# smd_isp_adapters.net
KiCad netlist of a schematic drawn in EAGLE
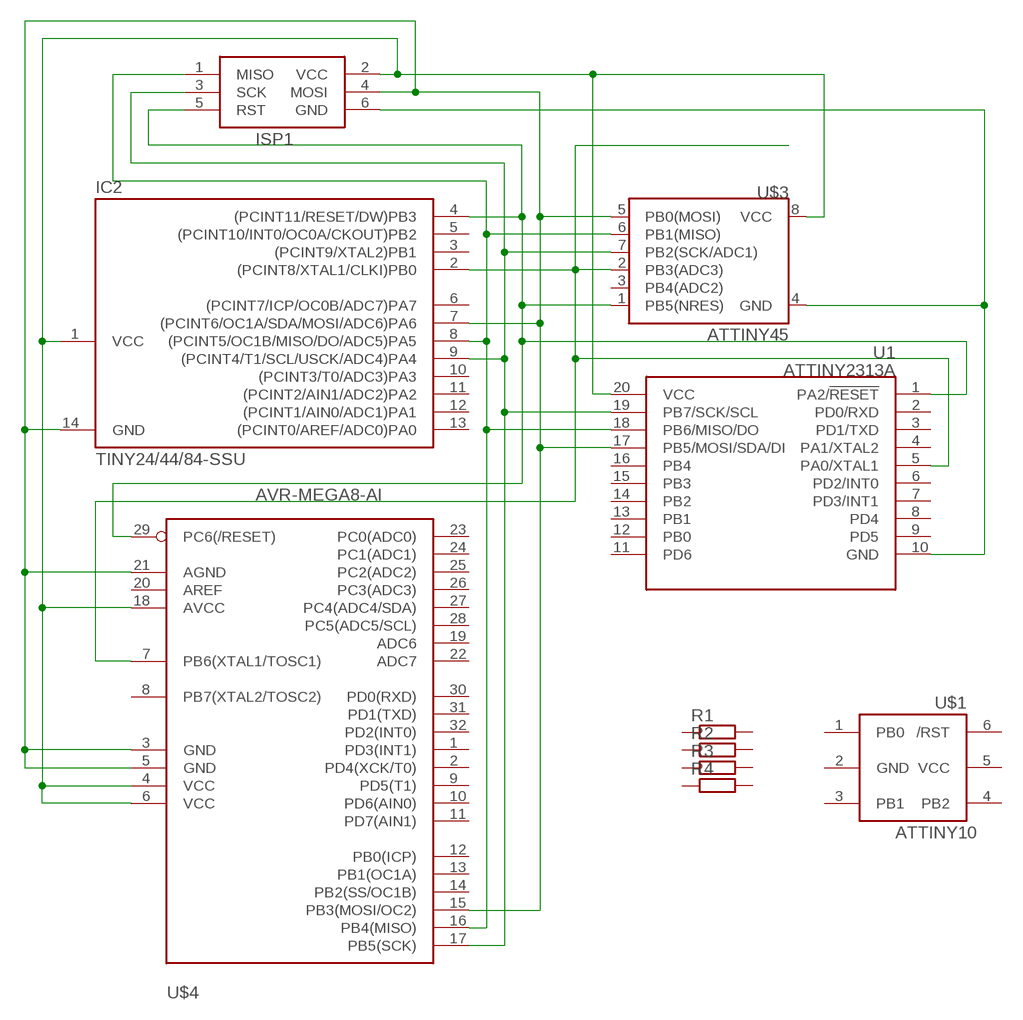
[diagram p0: schematic, sheet 1]

(export (version "E")
  (design (tool "Eeschema 10.0.6"))
  (components
    (comp (ref "IC2")
      (value "TINY24/44/84-SSU")
      (footprint "eagle-import:SOIC14")
      (libsource (lib "eagle-import") (part "TINY24/44/84-SSU"))
    )
    (comp (ref "ISP1")
      (value "AVRISP-6")
      (footprint "eagle-import:AVRISP")
      (libsource (lib "eagle-import") (part "AVRISP-6"))
    )
    (comp (ref "R1")
      (value "R-EU_R0805")
      (footprint "eagle-import:R0805")
      (libsource (lib "eagle-import") (part "R-EU_R0805"))
    )
    (comp (ref "R2")
      (value "R-EU_R0805")
      (footprint "eagle-import:R0805")
      (libsource (lib "eagle-import") (part "R-EU_R0805"))
    )
    (comp (ref "R3")
      (value "R-EU_R0805")
      (footprint "eagle-import:R0805")
      (libsource (lib "eagle-import") (part "R-EU_R0805"))
    )
    (comp (ref "R4")
      (value "R-EU_R0805")
      (footprint "eagle-import:R0805")
      (libsource (lib "eagle-import") (part "R-EU_R0805"))
    )
    (comp (ref "U$1")
      (value "ATTINY10")
      (footprint "eagle-import:SOT23-6")
      (libsource (lib "eagle-import") (part "ATTINY10"))
    )
    (comp (ref "U$3")
      (value "ATTINY45")
      (footprint "eagle-import:SO08-EIAJ")
      (libsource (lib "eagle-import") (part "ATTINY45"))
    )
    (comp (ref "U$4")
      (value "AVR-MEGA8-AI")
      (footprint "eagle-import:TQFP32-08")
      (libsource (lib "eagle-import") (part "AVR-MEGA8-AI"))
    )
    (comp (ref "U1")
      (value "ATTINY2313A")
      (footprint "eagle-import:SOP20W")
      (libsource (lib "eagle-import") (part "ATTINY2313A"))
    )
  )
  (nets
    (net (code "1") (name "/GND") (class "Default")
      (node (ref "U$1") (pin "2") (pinfunction "GND_2") (pintype "power_in"))
    )
    (net (code "2") (name "/VCC") (class "Default")
      (node (ref "U$1") (pin "5") (pinfunction "VCC_5") (pintype "power_in"))
    )
    (net (code "3") (name "Net-(IC2-(PCINT4{slash}T1{slash}SCL{slash}USCK{slash}ADC4)PA4)") (class "Default")
      (node (ref "IC2") (pin "9") (pinfunction "(PCINT4/T1/SCL/USCK/ADC4)PA4_9") (pintype "bidirectional"))
      (node (ref "ISP1") (pin "3") (pinfunction "SCK_3") (pintype "output"))
      (node (ref "U$3") (pin "7") (pinfunction "PB2(SCK/ADC1)_7") (pintype "bidirectional"))
      (node (ref "U$4") (pin "17") (pinfunction "PB5(SCK)_17") (pintype "bidirectional"))
      (node (ref "U1") (pin "19") (pinfunction "PB7/SCK/SCL_19") (pintype "bidirectional"))
    )
    (net (code "4") (name "Net-(IC2-(PCINT5{slash}OC1B{slash}MISO{slash}DO{slash}ADC5)PA5)") (class "Default")
      (node (ref "IC2") (pin "8") (pinfunction "(PCINT5/OC1B/MISO/DO/ADC5)PA5_8") (pintype "bidirectional"))
      (node (ref "ISP1") (pin "1") (pinfunction "MISO_1") (pintype "input"))
      (node (ref "U$3") (pin "6") (pinfunction "PB1(MISO)_6") (pintype "bidirectional"))
      (node (ref "U$4") (pin "16") (pinfunction "PB4(MISO)_16") (pintype "bidirectional"))
      (node (ref "U1") (pin "18") (pinfunction "PB6/MISO/DO_18") (pintype "bidirectional"))
    )
    (net (code "5") (name "Net-(IC2-(PCINT6{slash}OC1A{slash}SDA{slash}MOSI{slash}ADC6)PA6)") (class "Default")
      (node (ref "IC2") (pin "14") (pinfunction "GND_14") (pintype "power_in"))
      (node (ref "IC2") (pin "7") (pinfunction "(PCINT6/OC1A/SDA/MOSI/ADC6)PA6_7") (pintype "bidirectional"))
      (node (ref "ISP1") (pin "4") (pinfunction "MOSI_4") (pintype "output"))
      (node (ref "U$3") (pin "5") (pinfunction "PB0(MOSI)_5") (pintype "bidirectional"))
      (node (ref "U$4") (pin "15") (pinfunction "PB3(MOSI/OC2)_15") (pintype "bidirectional"))
      (node (ref "U$4") (pin "21") (pinfunction "AGND_21") (pintype "bidirectional"))
      (node (ref "U$4") (pin "3") (pinfunction "GND_3") (pintype "bidirectional"))
      (node (ref "U$4") (pin "5") (pinfunction "GND_5") (pintype "bidirectional"))
      (node (ref "U1") (pin "17") (pinfunction "PB5/MOSI/SDA/DI_17") (pintype "bidirectional"))
    )
    (net (code "6") (name "Net-(IC2-(PCINT8{slash}XTAL1{slash}CLKI)PB0)") (class "Default")
      (node (ref "IC2") (pin "2") (pinfunction "(PCINT8/XTAL1/CLKI)PB0_2") (pintype "bidirectional"))
      (node (ref "U$3") (pin "2") (pinfunction "PB3(ADC3)_2") (pintype "bidirectional"))
      (node (ref "U$4") (pin "7") (pinfunction "PB6(XTAL1/TOSC1)_7") (pintype "bidirectional"))
      (node (ref "U1") (pin "5") (pinfunction "PA0/XTAL1_5") (pintype "bidirectional"))
    )
    (net (code "7") (name "Net-(IC2-(PCINT11{slash}RESET{slash}DW)PB3)") (class "Default")
      (node (ref "IC2") (pin "4") (pinfunction "(PCINT11/RESET/DW)PB3_4") (pintype "bidirectional"))
      (node (ref "ISP1") (pin "5") (pinfunction "RST_5") (pintype "output"))
      (node (ref "U$3") (pin "1") (pinfunction "PB5(NRES)_1") (pintype "bidirectional"))
      (node (ref "U$4") (pin "29") (pinfunction "PC6(/RESET)_29") (pintype "bidirectional"))
      (node (ref "U1") (pin "1") (pinfunction "PA2/~{RESET}_1") (pintype "bidirectional"))
    )
    (net (code "8") (name "Net-(IC2-VCC)") (class "Default")
      (node (ref "IC2") (pin "1") (pinfunction "VCC_1") (pintype "power_in"))
      (node (ref "ISP1") (pin "2") (pinfunction "VCC_2") (pintype "power_in"))
      (node (ref "U$3") (pin "8") (pinfunction "VCC_8") (pintype "bidirectional"))
      (node (ref "U$4") (pin "18") (pinfunction "AVCC_18") (pintype "bidirectional"))
      (node (ref "U$4") (pin "4") (pinfunction "VCC_4") (pintype "bidirectional"))
      (node (ref "U$4") (pin "6") (pinfunction "VCC_6") (pintype "bidirectional"))
      (node (ref "U1") (pin "20") (pinfunction "VCC_20") (pintype "bidirectional"))
    )
    (net (code "9") (name "Net-(ISP1-GND)") (class "Default")
      (node (ref "ISP1") (pin "6") (pinfunction "GND_6") (pintype "power_in"))
      (node (ref "U$3") (pin "4") (pinfunction "GND_4") (pintype "bidirectional"))
      (node (ref "U1") (pin "10") (pinfunction "GND_10") (pintype "bidirectional"))
    )
    (net (code "10") (name "unconnected-(IC2-(PCINT0{slash}AREF{slash}ADC0)PA0-Pad13)") (class "Default")
      (node (ref "IC2") (pin "13") (pinfunction "(PCINT0/AREF/ADC0)PA0_13") (pintype "bidirectional"))
    )
    (net (code "11") (name "unconnected-(IC2-(PCINT1{slash}AIN0{slash}ADC1)PA1-Pad12)") (class "Default")
      (node (ref "IC2") (pin "12") (pinfunction "(PCINT1/AIN0/ADC1)PA1_12") (pintype "bidirectional"))
    )
    (net (code "12") (name "unconnected-(IC2-(PCINT2{slash}AIN1{slash}ADC2)PA2-Pad11)") (class "Default")
      (node (ref "IC2") (pin "11") (pinfunction "(PCINT2/AIN1/ADC2)PA2_11") (pintype "bidirectional"))
    )
    (net (code "13") (name "unconnected-(IC2-(PCINT3{slash}T0{slash}ADC3)PA3-Pad10)") (class "Default")
      (node (ref "IC2") (pin "10") (pinfunction "(PCINT3/T0/ADC3)PA3_10") (pintype "bidirectional"))
    )
    (net (code "14") (name "unconnected-(IC2-(PCINT7{slash}ICP{slash}OC0B{slash}ADC7)PA7-Pad6)") (class "Default")
      (node (ref "IC2") (pin "6") (pinfunction "(PCINT7/ICP/OC0B/ADC7)PA7_6") (pintype "bidirectional"))
    )
    (net (code "15") (name "unconnected-(IC2-(PCINT9{slash}XTAL2)PB1-Pad3)") (class "Default")
      (node (ref "IC2") (pin "3") (pinfunction "(PCINT9/XTAL2)PB1_3") (pintype "bidirectional"))
    )
    (net (code "16") (name "unconnected-(IC2-(PCINT10{slash}INT0{slash}OC0A{slash}CKOUT)PB2-Pad5)") (class "Default")
      (node (ref "IC2") (pin "5") (pinfunction "(PCINT10/INT0/OC0A/CKOUT)PB2_5") (pintype "bidirectional"))
    )
    (net (code "17") (name "unconnected-(R1-Pad1)") (class "Default")
      (node (ref "R1") (pin "1") (pinfunction "1_1") (pintype "passive"))
    )
    (net (code "18") (name "unconnected-(R1-Pad2)") (class "Default")
      (node (ref "R1") (pin "2") (pinfunction "2_2") (pintype "passive"))
    )
    (net (code "19") (name "unconnected-(R2-Pad1)") (class "Default")
      (node (ref "R2") (pin "1") (pinfunction "1_1") (pintype "passive"))
    )
    (net (code "20") (name "unconnected-(R2-Pad2)") (class "Default")
      (node (ref "R2") (pin "2") (pinfunction "2_2") (pintype "passive"))
    )
    (net (code "21") (name "unconnected-(R3-Pad1)") (class "Default")
      (node (ref "R3") (pin "1") (pinfunction "1_1") (pintype "passive"))
    )
    (net (code "22") (name "unconnected-(R3-Pad2)") (class "Default")
      (node (ref "R3") (pin "2") (pinfunction "2_2") (pintype "passive"))
    )
    (net (code "23") (name "unconnected-(R4-Pad1)") (class "Default")
      (node (ref "R4") (pin "1") (pinfunction "1_1") (pintype "passive"))
    )
    (net (code "24") (name "unconnected-(R4-Pad2)") (class "Default")
      (node (ref "R4") (pin "2") (pinfunction "2_2") (pintype "passive"))
    )
    (net (code "25") (name "unconnected-(U$1-PB0-Pad1)") (class "Default")
      (node (ref "U$1") (pin "1") (pinfunction "PB0_1") (pintype "bidirectional"))
    )
    (net (code "26") (name "unconnected-(U$1-PB1-Pad3)") (class "Default")
      (node (ref "U$1") (pin "3") (pinfunction "PB1_3") (pintype "bidirectional"))
    )
    (net (code "27") (name "unconnected-(U$1-PB2-Pad4)") (class "Default")
      (node (ref "U$1") (pin "4") (pinfunction "PB2_4") (pintype "bidirectional"))
    )
    (net (code "28") (name "unconnected-(U$1-{slash}RST-Pad6)") (class "Default")
      (node (ref "U$1") (pin "6") (pinfunction "/RST_6") (pintype "bidirectional"))
    )
    (net (code "29") (name "unconnected-(U$3-PB4(ADC2)-Pad3)") (class "Default")
      (node (ref "U$3") (pin "3") (pinfunction "PB4(ADC2)_3") (pintype "bidirectional"))
    )
    (net (code "30") (name "unconnected-(U$4-ADC6-Pad19)") (class "Default")
      (node (ref "U$4") (pin "19") (pinfunction "ADC6_19") (pintype "bidirectional"))
    )
    (net (code "31") (name "unconnected-(U$4-ADC7-Pad22)") (class "Default")
      (node (ref "U$4") (pin "22") (pinfunction "ADC7_22") (pintype "bidirectional"))
    )
    (net (code "32") (name "unconnected-(U$4-AREF-Pad20)") (class "Default")
      (node (ref "U$4") (pin "20") (pinfunction "AREF_20") (pintype "bidirectional"))
    )
    (net (code "33") (name "unconnected-(U$4-PB0(ICP)-Pad12)") (class "Default")
      (node (ref "U$4") (pin "12") (pinfunction "PB0(ICP)_12") (pintype "bidirectional"))
    )
    (net (code "34") (name "unconnected-(U$4-PB1(OC1A)-Pad13)") (class "Default")
      (node (ref "U$4") (pin "13") (pinfunction "PB1(OC1A)_13") (pintype "bidirectional"))
    )
    (net (code "35") (name "unconnected-(U$4-PB2(SS{slash}OC1B)-Pad14)") (class "Default")
      (node (ref "U$4") (pin "14") (pinfunction "PB2(SS/OC1B)_14") (pintype "bidirectional"))
    )
    (net (code "36") (name "unconnected-(U$4-PB7(XTAL2{slash}TOSC2)-Pad8)") (class "Default")
      (node (ref "U$4") (pin "8") (pinfunction "PB7(XTAL2/TOSC2)_8") (pintype "bidirectional"))
    )
    (net (code "37") (name "unconnected-(U$4-PC0(ADC0)-Pad23)") (class "Default")
      (node (ref "U$4") (pin "23") (pinfunction "PC0(ADC0)_23") (pintype "bidirectional"))
    )
    (net (code "38") (name "unconnected-(U$4-PC1(ADC1)-Pad24)") (class "Default")
      (node (ref "U$4") (pin "24") (pinfunction "PC1(ADC1)_24") (pintype "bidirectional"))
    )
    (net (code "39") (name "unconnected-(U$4-PC2(ADC2)-Pad25)") (class "Default")
      (node (ref "U$4") (pin "25") (pinfunction "PC2(ADC2)_25") (pintype "bidirectional"))
    )
    (net (code "40") (name "unconnected-(U$4-PC3(ADC3)-Pad26)") (class "Default")
      (node (ref "U$4") (pin "26") (pinfunction "PC3(ADC3)_26") (pintype "bidirectional"))
    )
    (net (code "41") (name "unconnected-(U$4-PC4(ADC4{slash}SDA)-Pad27)") (class "Default")
      (node (ref "U$4") (pin "27") (pinfunction "PC4(ADC4/SDA)_27") (pintype "bidirectional"))
    )
    (net (code "42") (name "unconnected-(U$4-PC5(ADC5{slash}SCL)-Pad28)") (class "Default")
      (node (ref "U$4") (pin "28") (pinfunction "PC5(ADC5/SCL)_28") (pintype "bidirectional"))
    )
    (net (code "43") (name "unconnected-(U$4-PD0(RXD)-Pad30)") (class "Default")
      (node (ref "U$4") (pin "30") (pinfunction "PD0(RXD)_30") (pintype "bidirectional"))
    )
    (net (code "44") (name "unconnected-(U$4-PD1(TXD)-Pad31)") (class "Default")
      (node (ref "U$4") (pin "31") (pinfunction "PD1(TXD)_31") (pintype "bidirectional"))
    )
    (net (code "45") (name "unconnected-(U$4-PD2(INT0)-Pad32)") (class "Default")
      (node (ref "U$4") (pin "32") (pinfunction "PD2(INT0)_32") (pintype "bidirectional"))
    )
    (net (code "46") (name "unconnected-(U$4-PD3(INT1)-Pad1)") (class "Default")
      (node (ref "U$4") (pin "1") (pinfunction "PD3(INT1)_1") (pintype "bidirectional"))
    )
    (net (code "47") (name "unconnected-(U$4-PD4(XCK{slash}T0)-Pad2)") (class "Default")
      (node (ref "U$4") (pin "2") (pinfunction "PD4(XCK/T0)_2") (pintype "bidirectional"))
    )
    (net (code "48") (name "unconnected-(U$4-PD5(T1)-Pad9)") (class "Default")
      (node (ref "U$4") (pin "9") (pinfunction "PD5(T1)_9") (pintype "bidirectional"))
    )
    (net (code "49") (name "unconnected-(U$4-PD6(AIN0)-Pad10)") (class "Default")
      (node (ref "U$4") (pin "10") (pinfunction "PD6(AIN0)_10") (pintype "bidirectional"))
    )
    (net (code "50") (name "unconnected-(U$4-PD7(AIN1)-Pad11)") (class "Default")
      (node (ref "U$4") (pin "11") (pinfunction "PD7(AIN1)_11") (pintype "bidirectional"))
    )
    (net (code "51") (name "unconnected-(U1-PA1{slash}XTAL2-Pad4)") (class "Default")
      (node (ref "U1") (pin "4") (pinfunction "PA1/XTAL2_4") (pintype "bidirectional"))
    )
    (net (code "52") (name "unconnected-(U1-PB0-Pad12)") (class "Default")
      (node (ref "U1") (pin "12") (pinfunction "PB0_12") (pintype "bidirectional"))
    )
    (net (code "53") (name "unconnected-(U1-PB1-Pad13)") (class "Default")
      (node (ref "U1") (pin "13") (pinfunction "PB1_13") (pintype "bidirectional"))
    )
    (net (code "54") (name "unconnected-(U1-PB2-Pad14)") (class "Default")
      (node (ref "U1") (pin "14") (pinfunction "PB2_14") (pintype "bidirectional"))
    )
    (net (code "55") (name "unconnected-(U1-PB3-Pad15)") (class "Default")
      (node (ref "U1") (pin "15") (pinfunction "PB3_15") (pintype "bidirectional"))
    )
    (net (code "56") (name "unconnected-(U1-PB4-Pad16)") (class "Default")
      (node (ref "U1") (pin "16") (pinfunction "PB4_16") (pintype "bidirectional"))
    )
    (net (code "57") (name "unconnected-(U1-PD0{slash}RXD-Pad2)") (class "Default")
      (node (ref "U1") (pin "2") (pinfunction "PD0/RXD_2") (pintype "bidirectional"))
    )
    (net (code "58") (name "unconnected-(U1-PD1{slash}TXD-Pad3)") (class "Default")
      (node (ref "U1") (pin "3") (pinfunction "PD1/TXD_3") (pintype "bidirectional"))
    )
    (net (code "59") (name "unconnected-(U1-PD2{slash}INT0-Pad6)") (class "Default")
      (node (ref "U1") (pin "6") (pinfunction "PD2/INT0_6") (pintype "bidirectional"))
    )
    (net (code "60") (name "unconnected-(U1-PD3{slash}INT1-Pad7)") (class "Default")
      (node (ref "U1") (pin "7") (pinfunction "PD3/INT1_7") (pintype "bidirectional"))
    )
    (net (code "61") (name "unconnected-(U1-PD4-Pad8)") (class "Default")
      (node (ref "U1") (pin "8") (pinfunction "PD4_8") (pintype "bidirectional"))
    )
    (net (code "62") (name "unconnected-(U1-PD5-Pad9)") (class "Default")
      (node (ref "U1") (pin "9") (pinfunction "PD5_9") (pintype "bidirectional"))
    )
    (net (code "63") (name "unconnected-(U1-PD6-Pad11)") (class "Default")
      (node (ref "U1") (pin "11") (pinfunction "PD6_11") (pintype "bidirectional"))
    )
  )
)
